# USB.net
KiCad netlist of a schematic drawn in Altium Designer
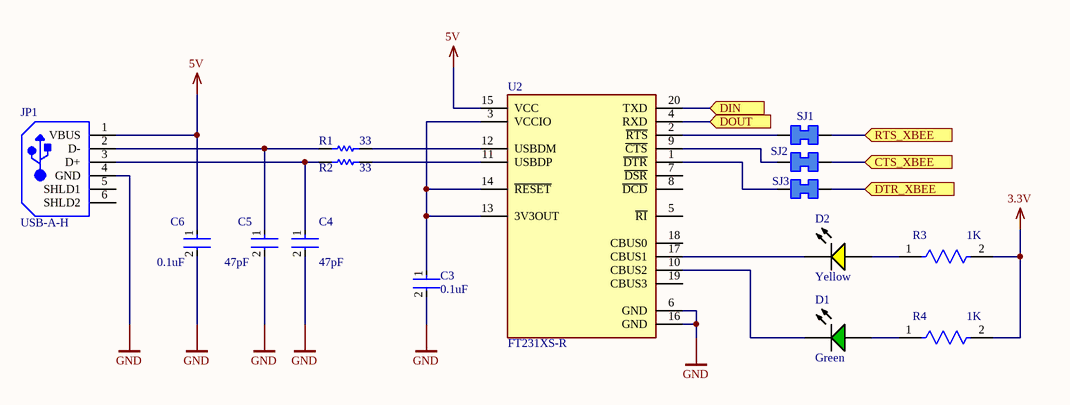
[diagram p0: USB.SchDoc]

(export (version "E")
  (design (tool "Eeschema 10.0.6"))
  (components
    (comp (ref "C3")
      (value "0.1uF")
      (footprint "FP-C0402-BB-MFG")
      (description "CAP CER 0.1UF 10V X5R 0402")
      (fields (field (name "MANUFACTURER") "Kemet") (field (name "TOLERANCE") "0.1"))
      (libsource (lib "Altium Content Vault") (part "b4654b650e69147ec39a6b967a45e02"))
    )
    (comp (ref "C4")
      (value "47pF")
      (footprint "FP-C0805C-DN-MFG")
      (description "CAP CER 47PF 50V C0G/NP0 0805")
      (fields
        (field (name "MANUFACTURER") "KEMET")
        (field (name "MANUFACTURER PART NUMBER") "C0805C470J5GACTU")
      )
      (libsource (lib "Altium Content Vault") (part "b4654b650e69147ec39a6b967a45e02"))
    )
    (comp (ref "C5")
      (value "47pF")
      (footprint "FP-C0805C-DN-MFG")
      (description "CAP CER 47PF 50V C0G/NP0 0805")
      (fields
        (field (name "MANUFACTURER") "KEMET")
        (field (name "MANUFACTURER PART NUMBER") "C0805C470J5GACTU")
      )
      (libsource (lib "Altium Content Vault") (part "b4654b650e69147ec39a6b967a45e02"))
    )
    (comp (ref "C6")
      (value "0.1uF")
      (footprint "FP-C0402-BB-MFG")
      (description "CAP CER 0.1UF 10V X5R 0402")
      (fields (field (name "MANUFACTURER") "Kemet") (field (name "TOLERANCE") "0.1"))
      (libsource (lib "Altium Content Vault") (part "b4654b650e69147ec39a6b967a45e02"))
    )
    (comp (ref "D1")
      (value "Green")
      (footprint "AVAG-HSMX-C170_V")
      (description "Chip LED, Green, 2.2 V, -40 to 85 degC, 2-Pin SMD, Pb-Free, Tape and Reel")
      (fields (field (name "MANUFACTURER") "Avago"))
      (libsource (lib "Altium Content Vault") (part "LED_GREEN_A1K2-2"))
    )
    (comp (ref "D2")
      (value "Yellow")
      (footprint "AVAG-HSMX-C190_V")
      (description "LED Uni-Color Yellow, 65 mW, 20 mA, -40 to 85 degC, 2-Pin SMD, RoHS, Tape and Reel")
      (fields (field (name "TOLERANCE") "1%"))
      (libsource (lib "Altium Content Vault") (part "LED-YELLOW-AK-2"))
    )
    (comp (ref "JP1")
      (value "USB-A-H")
      (footprint "TE-292303-1_V")
      (fields (field (name "MANUFACTURER") "TE Connectivity"))
      (libsource (lib "Altium Content Vault") (part "USB-4-2SHLD"))
    )
    (comp (ref "R1")
      (value "33")
      (footprint "RESC0603X26X15ML03T05")
      (fields (field (name "MANUFACTURER") "Panasonic") (field (name "PART NUMBER") "ERJ1GNF33R0C"))
      (libsource (lib "Altium Content Vault") (part "RES"))
    )
    (comp (ref "R2")
      (value "33")
      (footprint "RESC0603X26X15ML03T05")
      (fields (field (name "MANUFACTURER") "Panasonic") (field (name "PART NUMBER") "ERJ1GNF33R0C"))
      (libsource (lib "Altium Content Vault") (part "RES"))
    )
    (comp (ref "R3")
      (value "1K")
      (footprint "FP-ERJ1GN-IPC_C")
      (description "RES SMD 1K OHM 1% 1/20W 0201")
      (fields (field (name "TOLERANCE") "1%"))
      (libsource (lib "Altium Content Vault") (part "1029c3af85768c4190bb7ad29bc67b5"))
    )
    (comp (ref "R4")
      (value "1K")
      (footprint "FP-ERJ1GN-IPC_C")
      (description "RES SMD 1K OHM 1% 1/20W 0201")
      (fields (field (name "TOLERANCE") "1%"))
      (libsource (lib "Altium Content Vault") (part "1029c3af85768c4190bb7ad29bc67b5"))
    )
    (comp (ref "SJ1")
      (value "Solder Jumper")
      (footprint "Solder Jumper-Footprint-1")
      (description "2 pad Solder Jumper")
      (libsource (lib "Shuvendu Das") (part "Solder Jumper"))
    )
    (comp (ref "SJ2")
      (value "Solder Jumper")
      (footprint "Solder Jumper-Footprint-1")
      (description "2 pad Solder Jumper")
      (libsource (lib "Shuvendu Das") (part "Solder Jumper"))
    )
    (comp (ref "SJ3")
      (value "Solder Jumper")
      (footprint "Solder Jumper-Footprint-1")
      (description "2 pad Solder Jumper")
      (libsource (lib "Shuvendu Das") (part "Solder Jumper"))
    )
    (comp (ref "U2")
      (value "FT231XS-R")
      (footprint "FP-SSOP-20-MFG")
      (description "IC USB SERIAL FULL UART 20SSOP")
      (libsource (lib "Altium Content Vault") (part "6ea930917329caabf1041b50a9b81b2"))
    )
  )
  (nets
    (net (code "1") (name "/CTS_XBEE") (class "Default")
      (node (ref "SJ2") (pin "2") (pinfunction "2_2") (pintype "passive"))
    )
    (net (code "2") (name "/DIN") (class "Default")
      (node (ref "U2") (pin "20") (pinfunction "TXD_20") (pintype "passive"))
    )
    (net (code "3") (name "/DOUT") (class "Default")
      (node (ref "U2") (pin "4") (pinfunction "RXD_4") (pintype "passive"))
    )
    (net (code "4") (name "/DTR_XBEE") (class "Default")
      (node (ref "SJ3") (pin "2") (pinfunction "2_2") (pintype "passive"))
    )
    (net (code "5") (name "/RTS_XBEE") (class "Default")
      (node (ref "SJ1") (pin "2") (pinfunction "2_2") (pintype "passive"))
    )
    (net (code "6") (name "3.3V") (class "Default")
      (node (ref "R3") (pin "2") (pinfunction "2_2") (pintype "passive"))
      (node (ref "R4") (pin "2") (pinfunction "2_2") (pintype "passive"))
    )
    (net (code "7") (name "5V") (class "Default")
      (node (ref "C6") (pin "1") (pinfunction "1_1") (pintype "passive"))
      (node (ref "JP1") (pin "1") (pinfunction "VBUS_1") (pintype "passive"))
      (node (ref "U2") (pin "15") (pinfunction "VCC_15") (pintype "power_in"))
    )
    (net (code "8") (name "GND") (class "Default")
      (node (ref "C3") (pin "2") (pinfunction "2_2") (pintype "passive"))
      (node (ref "C4") (pin "2") (pinfunction "2_2") (pintype "passive"))
      (node (ref "C5") (pin "2") (pinfunction "2_2") (pintype "passive"))
      (node (ref "C6") (pin "2") (pinfunction "2_2") (pintype "passive"))
      (node (ref "JP1") (pin "4") (pinfunction "GND_4") (pintype "passive"))
      (node (ref "U2") (pin "16") (pinfunction "GND_16") (pintype "power_in"))
      (node (ref "U2") (pin "6") (pinfunction "GND_6") (pintype "power_in"))
    )
    (net (code "9") (name "Net-(D1-A)") (class "Default")
      (node (ref "D1") (pin "1") (pinfunction "A_1") (pintype "passive"))
      (node (ref "R4") (pin "1") (pinfunction "1_1") (pintype "passive"))
    )
    (net (code "10") (name "Net-(D1-K)") (class "Default")
      (node (ref "D1") (pin "2") (pinfunction "K_2") (pintype "passive"))
      (node (ref "U2") (pin "10") (pinfunction "CBUS2_10") (pintype "passive"))
    )
    (net (code "11") (name "Net-(D2-A)") (class "Default")
      (node (ref "D2") (pin "1") (pinfunction "A_1") (pintype "passive"))
      (node (ref "R3") (pin "1") (pinfunction "1_1") (pintype "passive"))
    )
    (net (code "12") (name "Net-(D2-K)") (class "Default")
      (node (ref "D2") (pin "2") (pinfunction "K_2") (pintype "passive"))
      (node (ref "U2") (pin "17") (pinfunction "CBUS1_17") (pintype "passive"))
    )
    (net (code "13") (name "Net-(JP1-D+)") (class "Default")
      (node (ref "C4") (pin "1") (pinfunction "1_1") (pintype "passive"))
      (node (ref "JP1") (pin "3") (pinfunction "D+_3") (pintype "passive"))
      (node (ref "R2") (pin "1") (pinfunction "1_1") (pintype "passive"))
    )
    (net (code "14") (name "Net-(JP1-D-)") (class "Default")
      (node (ref "C5") (pin "1") (pinfunction "1_1") (pintype "passive"))
      (node (ref "JP1") (pin "2") (pinfunction "D-_2") (pintype "passive"))
      (node (ref "R1") (pin "1") (pinfunction "1_1") (pintype "passive"))
    )
    (net (code "15") (name "Net-(U2-3V3OUT)") (class "Default")
      (node (ref "C3") (pin "1") (pinfunction "1_1") (pintype "passive"))
      (node (ref "U2") (pin "13") (pinfunction "3V3OUT_13") (pintype "passive"))
      (node (ref "U2") (pin "14") (pinfunction "~{RESET}_14") (pintype "passive"))
      (node (ref "U2") (pin "3") (pinfunction "VCCIO_3") (pintype "power_in"))
    )
    (net (code "16") (name "Net-(U2-USBDM)") (class "Default")
      (node (ref "R1") (pin "2") (pinfunction "2_2") (pintype "passive"))
      (node (ref "U2") (pin "12") (pinfunction "USBDM_12") (pintype "passive"))
    )
    (net (code "17") (name "Net-(U2-USBDP)") (class "Default")
      (node (ref "R2") (pin "2") (pinfunction "2_2") (pintype "passive"))
      (node (ref "U2") (pin "11") (pinfunction "USBDP_11") (pintype "passive"))
    )
    (net (code "18") (name "Net-(U2-~{CTS})") (class "Default")
      (node (ref "SJ2") (pin "1") (pinfunction "1_1") (pintype "passive"))
      (node (ref "U2") (pin "9") (pinfunction "~{CTS}_9") (pintype "passive"))
    )
    (net (code "19") (name "Net-(U2-~{DTR})") (class "Default")
      (node (ref "SJ3") (pin "1") (pinfunction "1_1") (pintype "passive"))
      (node (ref "U2") (pin "1") (pinfunction "~{DTR}_1") (pintype "passive"))
    )
    (net (code "20") (name "Net-(U2-~{RTS})") (class "Default")
      (node (ref "SJ1") (pin "1") (pinfunction "1_1") (pintype "passive"))
      (node (ref "U2") (pin "2") (pinfunction "~{RTS}_2") (pintype "passive"))
    )
    (net (code "21") (name "unconnected-(JP1-SHLD1-Pad5)") (class "Default")
      (node (ref "JP1") (pin "5") (pinfunction "SHLD1_5") (pintype "passive"))
    )
    (net (code "22") (name "unconnected-(JP1-SHLD2-Pad6)") (class "Default")
      (node (ref "JP1") (pin "6") (pinfunction "SHLD2_6") (pintype "passive"))
    )
    (net (code "23") (name "unconnected-(U2-CBUS0-Pad18)") (class "Default")
      (node (ref "U2") (pin "18") (pinfunction "CBUS0_18") (pintype "passive"))
    )
    (net (code "24") (name "unconnected-(U2-CBUS3-Pad19)") (class "Default")
      (node (ref "U2") (pin "19") (pinfunction "CBUS3_19") (pintype "passive"))
    )
    (net (code "25") (name "unconnected-(U2-~{DCD}-Pad8)") (class "Default")
      (node (ref "U2") (pin "8") (pinfunction "~{DCD}_8") (pintype "passive"))
    )
    (net (code "26") (name "unconnected-(U2-~{DSR}-Pad7)") (class "Default")
      (node (ref "U2") (pin "7") (pinfunction "~{DSR}_7") (pintype "passive"))
    )
    (net (code "27") (name "unconnected-(U2-~{RI}-Pad5)") (class "Default")
      (node (ref "U2") (pin "5") (pinfunction "~{RI}_5") (pintype "passive"))
    )
  )
)
